# HW2_Schematic.net
KiCad netlist of a schematic drawn in EAGLE
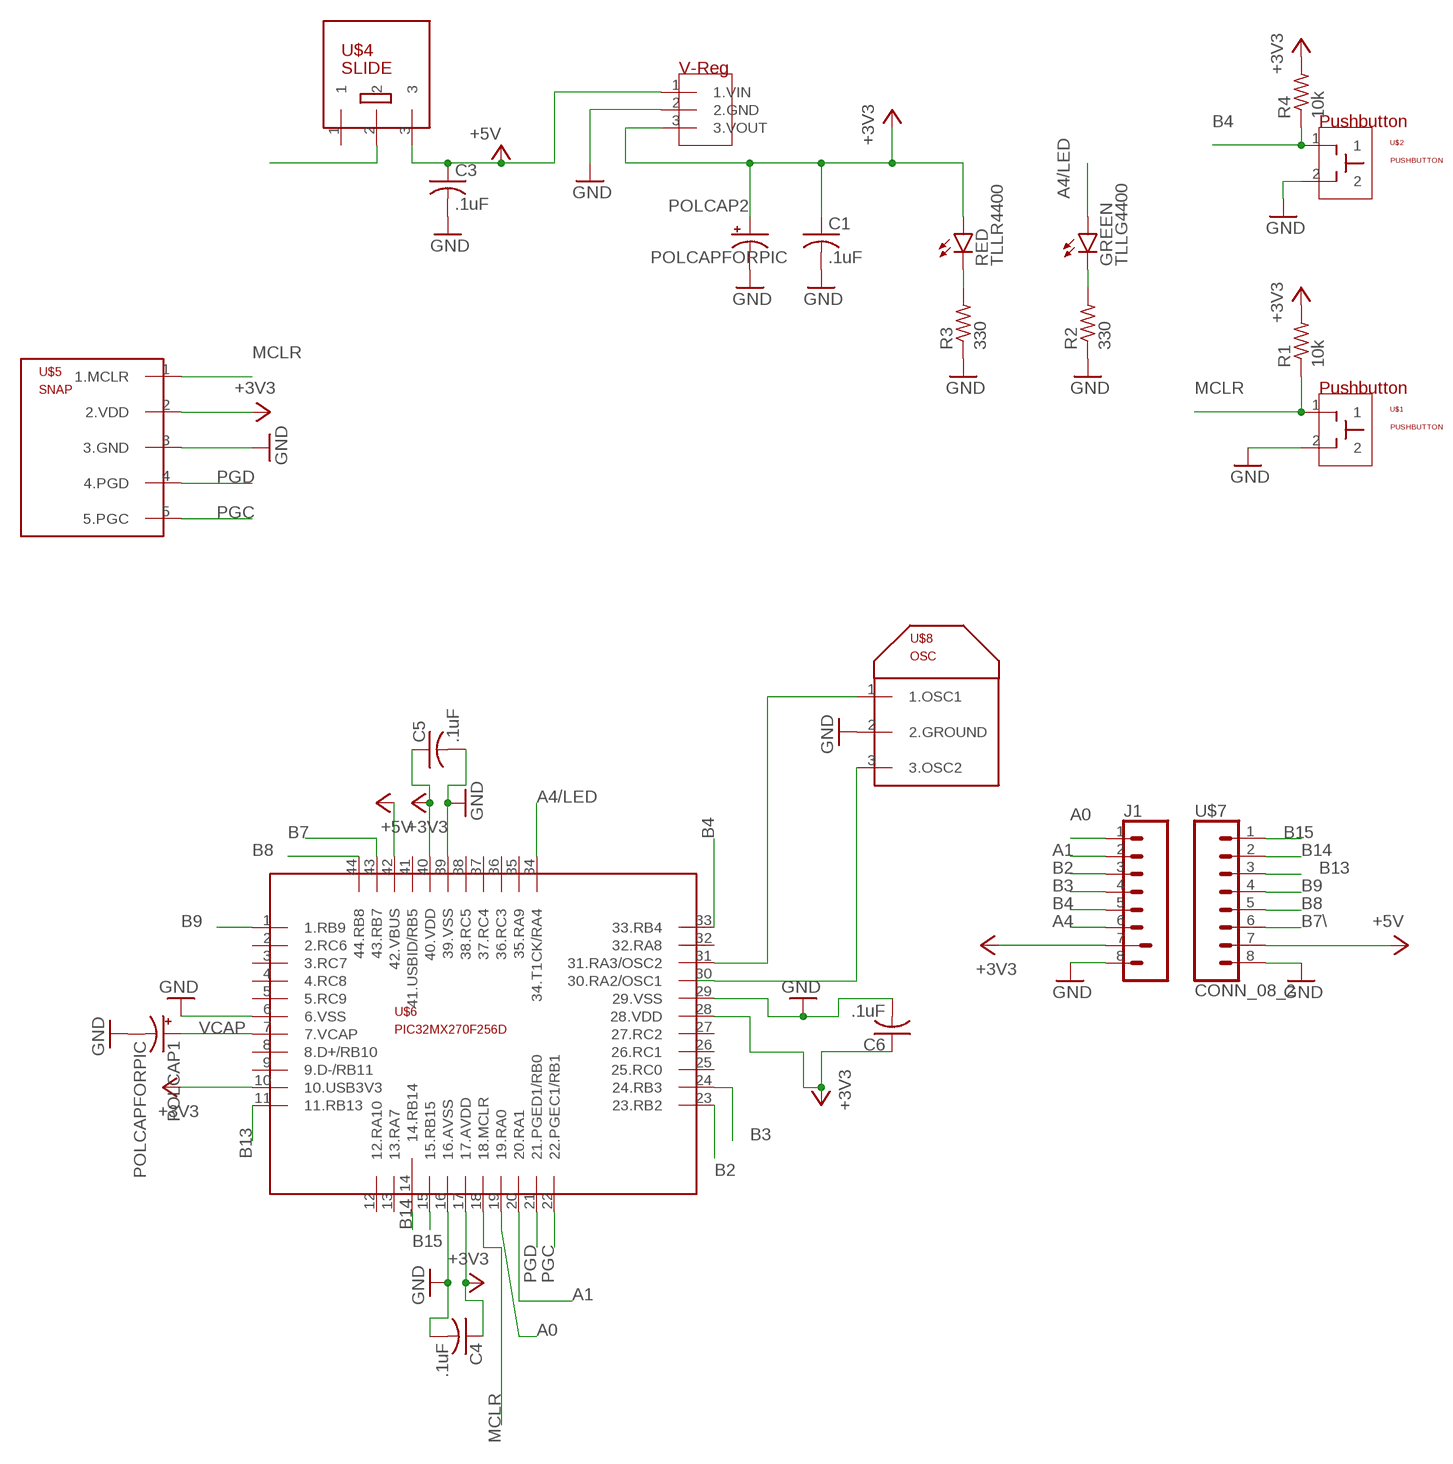
[diagram p0: schematic, sheet 1]

(export (version "E")
  (design (tool "Eeschema 10.0.6"))
  (components
    (comp (ref "C1")
      (value ".1uF")
      (footprint "eagle-import:C025-030X050")
      (libsource (lib "eagle-import") (part "rcl_334_C-US025-030X050"))
    )
    (comp (ref "C3")
      (value ".1uF")
      (footprint "eagle-import:C025-030X050")
      (libsource (lib "eagle-import") (part "rcl_334_C-US025-030X050"))
    )
    (comp (ref "C4")
      (value ".1uF")
      (footprint "eagle-import:C025-024X044")
      (libsource (lib "eagle-import") (part "C-US025-024X044"))
    )
    (comp (ref "C5")
      (value ".1uF")
      (footprint "eagle-import:C025-024X044")
      (libsource (lib "eagle-import") (part "C-US025-024X044"))
    )
    (comp (ref "C6")
      (value ".1uF")
      (footprint "eagle-import:C025-024X044")
      (libsource (lib "eagle-import") (part "C-US025-024X044"))
    )
    (comp (ref "GREEN")
      (value "TLLG4400")
      (footprint "eagle-import:LED3MM")
      (fields (field (name "MF") "VISHAY SEMICONDUCTOR"))
      (libsource (lib "eagle-import") (part "TLLG4400"))
    )
    (comp (ref "J1")
      (value "CONN_08")
      (footprint "eagle-import:CONN08")
      (libsource (lib "eagle-import") (part "CONN_08"))
    )
    (comp (ref "POLCAP1")
      (value "POLCAPFORPIC")
      (footprint "eagle-import:POLARIZEDCAPFORPIC")
      (libsource (lib "eagle-import") (part "POLCAPFORPIC"))
    )
    (comp (ref "POLCAP2")
      (value "POLCAPFORPIC")
      (footprint "eagle-import:POLARIZEDCAPFORPIC")
      (libsource (lib "eagle-import") (part "POLCAPFORPIC"))
    )
    (comp (ref "R1")
      (value "10k")
      (footprint "eagle-import:0207_10")
      (libsource (lib "eagle-import") (part "R-US_0207/10"))
    )
    (comp (ref "R2")
      (value "330")
      (footprint "eagle-import:0207_10")
      (libsource (lib "eagle-import") (part "R-US_0207/10"))
    )
    (comp (ref "R3")
      (value "330")
      (footprint "eagle-import:0207_10")
      (libsource (lib "eagle-import") (part "R-US_0207/10"))
    )
    (comp (ref "R4")
      (value "10k")
      (footprint "eagle-import:0207_10")
      (libsource (lib "eagle-import") (part "R-US_0207/10"))
    )
    (comp (ref "RED")
      (value "TLLR4400")
      (footprint "eagle-import:LED3MM")
      (fields (field (name "MF") "VISHAY SEMICONDUCTOR"))
      (libsource (lib "eagle-import") (part "TLLR4400"))
    )
    (comp (ref "U$1")
      (value "PUSHBUTTON")
      (footprint "eagle-import:PUSHBUTTON")
      (libsource (lib "eagle-import") (part "PUSHBUTTON"))
    )
    (comp (ref "U$2")
      (value "PUSHBUTTON")
      (footprint "eagle-import:PUSHBUTTON")
      (libsource (lib "eagle-import") (part "PUSHBUTTON"))
    )
    (comp (ref "U$3")
      (value "VOTAGEREG")
      (footprint "eagle-import:V-REG")
      (libsource (lib "eagle-import") (part "VOTAGEREG"))
    )
    (comp (ref "U$4")
      (value "SLIDE")
      (footprint "eagle-import:SLIDE")
      (libsource (lib "eagle-import") (part "SLIDE"))
    )
    (comp (ref "U$5")
      (value "SNAP")
      (footprint "eagle-import:SNAP")
      (libsource (lib "eagle-import") (part "SNAP"))
    )
    (comp (ref "U$6")
      (value "PIC32MX270F256D")
      (footprint "eagle-import:PIC_44-PIN")
      (libsource (lib "eagle-import") (part "PIC32MX270F256D"))
    )
    (comp (ref "U$7")
      (value "CONN_08_2")
      (footprint "eagle-import:CONN08")
      (libsource (lib "eagle-import") (part "CONN_08_2"))
    )
    (comp (ref "U$8")
      (value "OSC")
      (footprint "eagle-import:OSC")
      (libsource (lib "eagle-import") (part "OSC"))
    )
  )
  (nets
    (net (code "1") (name "+3V3") (class "Default")
      (node (ref "C1") (pin "1") (pinfunction "1_1") (pintype "passive"))
      (node (ref "C4") (pin "1") (pinfunction "1_1") (pintype "passive"))
      (node (ref "C5") (pin "1") (pinfunction "1_1") (pintype "passive"))
      (node (ref "C6") (pin "1") (pinfunction "1_1") (pintype "passive"))
      (node (ref "J1") (pin "7") (pinfunction "7.3V3_7") (pintype "passive"))
      (node (ref "POLCAP2") (pin "1") (pinfunction "+_1") (pintype "passive"))
      (node (ref "R1") (pin "2") (pinfunction "2_2") (pintype "passive"))
      (node (ref "R4") (pin "2") (pinfunction "2_2") (pintype "passive"))
      (node (ref "RED") (pin "A") (pinfunction "A_A") (pintype "passive"))
      (node (ref "U$3") (pin "3") (pinfunction "3.VOUT_3") (pintype "bidirectional"))
      (node (ref "U$5") (pin "2") (pinfunction "2.VDD_2") (pintype "bidirectional"))
      (node (ref "U$6") (pin "10") (pinfunction "10.USB3V3_10") (pintype "bidirectional"))
      (node (ref "U$6") (pin "17") (pinfunction "17.AVDD_17") (pintype "bidirectional"))
      (node (ref "U$6") (pin "28") (pinfunction "28.VDD_28") (pintype "bidirectional"))
      (node (ref "U$6") (pin "40") (pinfunction "40.VDD_40") (pintype "bidirectional"))
    )
    (net (code "2") (name "+5V") (class "Default")
      (node (ref "C3") (pin "1") (pinfunction "1_1") (pintype "passive"))
      (node (ref "U$3") (pin "1") (pinfunction "1.VIN_1") (pintype "bidirectional"))
      (node (ref "U$4") (pin "3") (pinfunction "3_3") (pintype "bidirectional"))
      (node (ref "U$6") (pin "42") (pinfunction "42.VBUS_42") (pintype "bidirectional"))
      (node (ref "U$7") (pin "7") (pinfunction "7.5V_7") (pintype "passive"))
    )
    (net (code "3") (name "/A0") (class "Default")
      (node (ref "J1") (pin "1") (pinfunction "1.A0_1") (pintype "passive"))
      (node (ref "U$6") (pin "19") (pinfunction "19.RA0_19") (pintype "bidirectional"))
    )
    (net (code "4") (name "/A1") (class "Default")
      (node (ref "J1") (pin "2") (pinfunction "2.A1_2") (pintype "passive"))
      (node (ref "U$6") (pin "20") (pinfunction "20.RA1_20") (pintype "bidirectional"))
    )
    (net (code "5") (name "/A4") (class "Default")
      (node (ref "J1") (pin "6") (pinfunction "6.A4_6") (pintype "passive"))
    )
    (net (code "6") (name "/A4{slash}LED") (class "Default")
      (node (ref "GREEN") (pin "A") (pinfunction "A_A") (pintype "passive"))
      (node (ref "U$6") (pin "34") (pinfunction "34.T1CK/RA4_34") (pintype "bidirectional"))
    )
    (net (code "7") (name "/B2") (class "Default")
      (node (ref "J1") (pin "3") (pinfunction "3.B2_3") (pintype "passive"))
      (node (ref "U$6") (pin "23") (pinfunction "23.RB2_23") (pintype "bidirectional"))
    )
    (net (code "8") (name "/B3") (class "Default")
      (node (ref "J1") (pin "4") (pinfunction "4.B3_4") (pintype "passive"))
      (node (ref "U$6") (pin "24") (pinfunction "24.RB3_24") (pintype "bidirectional"))
    )
    (net (code "9") (name "/B4") (class "Default")
      (node (ref "J1") (pin "5") (pinfunction "5.B4_5") (pintype "passive"))
      (node (ref "R4") (pin "1") (pinfunction "1_1") (pintype "passive"))
      (node (ref "U$2") (pin "1") (pinfunction "1_1") (pintype "bidirectional"))
      (node (ref "U$6") (pin "33") (pinfunction "33.RB4_33") (pintype "bidirectional"))
    )
    (net (code "10") (name "/B7") (class "Default")
      (node (ref "U$6") (pin "43") (pinfunction "43.RB7_43") (pintype "bidirectional"))
    )
    (net (code "11") (name "/B7\\") (class "Default")
      (node (ref "U$7") (pin "6") (pinfunction "6.B7_6") (pintype "passive"))
    )
    (net (code "12") (name "/B8") (class "Default")
      (node (ref "U$6") (pin "44") (pinfunction "44.RB8_44") (pintype "bidirectional"))
      (node (ref "U$7") (pin "5") (pinfunction "5.B8_5") (pintype "passive"))
    )
    (net (code "13") (name "/B9") (class "Default")
      (node (ref "U$6") (pin "1") (pinfunction "1.RB9_1") (pintype "bidirectional"))
      (node (ref "U$7") (pin "4") (pinfunction "4.B9_4") (pintype "passive"))
    )
    (net (code "14") (name "/B13") (class "Default")
      (node (ref "U$6") (pin "11") (pinfunction "11.RB13_11") (pintype "bidirectional"))
      (node (ref "U$7") (pin "3") (pinfunction "3.B13_3") (pintype "passive"))
    )
    (net (code "15") (name "/B14") (class "Default")
      (node (ref "U$6") (pin "14") (pinfunction "14.RB14_14") (pintype "bidirectional"))
      (node (ref "U$7") (pin "2") (pinfunction "2.B14_2") (pintype "passive"))
    )
    (net (code "16") (name "/B15") (class "Default")
      (node (ref "U$6") (pin "15") (pinfunction "15.RB15_15") (pintype "bidirectional"))
      (node (ref "U$7") (pin "1") (pinfunction "1.B15_1") (pintype "passive"))
    )
    (net (code "17") (name "/MCLR") (class "Default")
      (node (ref "R1") (pin "1") (pinfunction "1_1") (pintype "passive"))
      (node (ref "U$1") (pin "1") (pinfunction "1_1") (pintype "bidirectional"))
      (node (ref "U$5") (pin "1") (pinfunction "1.MCLR_1") (pintype "bidirectional"))
      (node (ref "U$6") (pin "18") (pinfunction "18.MCLR_18") (pintype "bidirectional"))
    )
    (net (code "18") (name "/PGC") (class "Default")
      (node (ref "U$5") (pin "5") (pinfunction "5.PGC_5") (pintype "bidirectional"))
      (node (ref "U$6") (pin "22") (pinfunction "22.PGEC1/RB1_22") (pintype "bidirectional"))
    )
    (net (code "19") (name "/PGD") (class "Default")
      (node (ref "U$5") (pin "4") (pinfunction "4.PGD_4") (pintype "bidirectional"))
      (node (ref "U$6") (pin "21") (pinfunction "21.PGED1/RB0_21") (pintype "bidirectional"))
    )
    (net (code "20") (name "/VCAP") (class "Default")
      (node (ref "POLCAP1") (pin "1") (pinfunction "+_1") (pintype "passive"))
      (node (ref "U$6") (pin "7") (pinfunction "7.VCAP_7") (pintype "bidirectional"))
    )
    (net (code "21") (name "GND") (class "Default")
      (node (ref "C1") (pin "2") (pinfunction "2_2") (pintype "passive"))
      (node (ref "C3") (pin "2") (pinfunction "2_2") (pintype "passive"))
      (node (ref "C4") (pin "2") (pinfunction "2_2") (pintype "passive"))
      (node (ref "C5") (pin "2") (pinfunction "2_2") (pintype "passive"))
      (node (ref "C6") (pin "2") (pinfunction "2_2") (pintype "passive"))
      (node (ref "J1") (pin "8") (pinfunction "8.GND_8") (pintype "passive"))
      (node (ref "POLCAP1") (pin "2") (pinfunction "-_2") (pintype "passive"))
      (node (ref "POLCAP2") (pin "2") (pinfunction "-_2") (pintype "passive"))
      (node (ref "R2") (pin "1") (pinfunction "1_1") (pintype "passive"))
      (node (ref "R3") (pin "1") (pinfunction "1_1") (pintype "passive"))
      (node (ref "U$1") (pin "2") (pinfunction "2_2") (pintype "bidirectional"))
      (node (ref "U$2") (pin "2") (pinfunction "2_2") (pintype "bidirectional"))
      (node (ref "U$3") (pin "2") (pinfunction "2.GND_2") (pintype "bidirectional"))
      (node (ref "U$5") (pin "3") (pinfunction "3.GND_3") (pintype "bidirectional"))
      (node (ref "U$6") (pin "16") (pinfunction "16.AVSS_16") (pintype "bidirectional"))
      (node (ref "U$6") (pin "29") (pinfunction "29.VSS_29") (pintype "bidirectional"))
      (node (ref "U$6") (pin "39") (pinfunction "39.VSS_39") (pintype "bidirectional"))
      (node (ref "U$6") (pin "6") (pinfunction "6.VSS_6") (pintype "bidirectional"))
      (node (ref "U$7") (pin "8") (pinfunction "8.GND_8") (pintype "passive"))
      (node (ref "U$8") (pin "2") (pinfunction "2.GROUND_2") (pintype "bidirectional"))
    )
    (net (code "22") (name "Net-(GREEN-C)") (class "Default")
      (node (ref "GREEN") (pin "K") (pinfunction "C_K") (pintype "passive"))
      (node (ref "R2") (pin "2") (pinfunction "2_2") (pintype "passive"))
    )
    (net (code "23") (name "Net-(RED-C)") (class "Default")
      (node (ref "R3") (pin "2") (pinfunction "2_2") (pintype "passive"))
      (node (ref "RED") (pin "K") (pinfunction "C_K") (pintype "passive"))
    )
    (net (code "24") (name "Net-(U$6-30.RA2{slash}OSC1)") (class "Default")
      (node (ref "U$6") (pin "30") (pinfunction "30.RA2/OSC1_30") (pintype "bidirectional"))
      (node (ref "U$8") (pin "3") (pinfunction "3.OSC2_3") (pintype "bidirectional"))
    )
    (net (code "25") (name "Net-(U$6-31.RA3{slash}OSC2)") (class "Default")
      (node (ref "U$6") (pin "31") (pinfunction "31.RA3/OSC2_31") (pintype "bidirectional"))
      (node (ref "U$8") (pin "1") (pinfunction "1.OSC1_1") (pintype "bidirectional"))
    )
    (net (code "26") (name "unconnected-(U$4-Pad1)") (class "Default")
      (node (ref "U$4") (pin "1") (pinfunction "1_1") (pintype "bidirectional"))
    )
    (net (code "27") (name "unconnected-(U$4-Pad2)") (class "Default")
      (node (ref "U$4") (pin "2") (pinfunction "2_2") (pintype "bidirectional"))
    )
    (net (code "28") (name "unconnected-(U$6-2.RC6-Pad2)") (class "Default")
      (node (ref "U$6") (pin "2") (pinfunction "2.RC6_2") (pintype "bidirectional"))
    )
    (net (code "29") (name "unconnected-(U$6-3.RC7-Pad3)") (class "Default")
      (node (ref "U$6") (pin "3") (pinfunction "3.RC7_3") (pintype "bidirectional"))
    )
    (net (code "30") (name "unconnected-(U$6-4.RC8-Pad4)") (class "Default")
      (node (ref "U$6") (pin "4") (pinfunction "4.RC8_4") (pintype "bidirectional"))
    )
    (net (code "31") (name "unconnected-(U$6-5.RC9-Pad5)") (class "Default")
      (node (ref "U$6") (pin "5") (pinfunction "5.RC9_5") (pintype "bidirectional"))
    )
    (net (code "32") (name "unconnected-(U$6-8.D+{slash}RB10-Pad8)") (class "Default")
      (node (ref "U$6") (pin "8") (pinfunction "8.D+/RB10_8") (pintype "bidirectional"))
    )
    (net (code "33") (name "unconnected-(U$6-9.D-{slash}RB11-Pad9)") (class "Default")
      (node (ref "U$6") (pin "9") (pinfunction "9.D-/RB11_9") (pintype "bidirectional"))
    )
    (net (code "34") (name "unconnected-(U$6-12.RA10-Pad12)") (class "Default")
      (node (ref "U$6") (pin "12") (pinfunction "12.RA10_12") (pintype "bidirectional"))
    )
    (net (code "35") (name "unconnected-(U$6-13.RA7-Pad13)") (class "Default")
      (node (ref "U$6") (pin "13") (pinfunction "13.RA7_13") (pintype "bidirectional"))
    )
    (net (code "36") (name "unconnected-(U$6-25.RC0-Pad25)") (class "Default")
      (node (ref "U$6") (pin "25") (pinfunction "25.RC0_25") (pintype "bidirectional"))
    )
    (net (code "37") (name "unconnected-(U$6-26.RC1-Pad26)") (class "Default")
      (node (ref "U$6") (pin "26") (pinfunction "26.RC1_26") (pintype "bidirectional"))
    )
    (net (code "38") (name "unconnected-(U$6-27.RC2-Pad27)") (class "Default")
      (node (ref "U$6") (pin "27") (pinfunction "27.RC2_27") (pintype "bidirectional"))
    )
    (net (code "39") (name "unconnected-(U$6-32.RA8-Pad32)") (class "Default")
      (node (ref "U$6") (pin "32") (pinfunction "32.RA8_32") (pintype "bidirectional"))
    )
    (net (code "40") (name "unconnected-(U$6-35.RA9-Pad35)") (class "Default")
      (node (ref "U$6") (pin "35") (pinfunction "35.RA9_35") (pintype "bidirectional"))
    )
    (net (code "41") (name "unconnected-(U$6-36.RC3-Pad36)") (class "Default")
      (node (ref "U$6") (pin "36") (pinfunction "36.RC3_36") (pintype "bidirectional"))
    )
    (net (code "42") (name "unconnected-(U$6-37.RC4-Pad37)") (class "Default")
      (node (ref "U$6") (pin "37") (pinfunction "37.RC4_37") (pintype "bidirectional"))
    )
    (net (code "43") (name "unconnected-(U$6-38.RC5-Pad38)") (class "Default")
      (node (ref "U$6") (pin "38") (pinfunction "38.RC5_38") (pintype "bidirectional"))
    )
    (net (code "44") (name "unconnected-(U$6-41.USBID{slash}RB5-Pad41)") (class "Default")
      (node (ref "U$6") (pin "41") (pinfunction "41.USBID/RB5_41") (pintype "bidirectional"))
    )
  )
)
